# test2.net
KiCad netlist of a schematic drawn in EAGLE
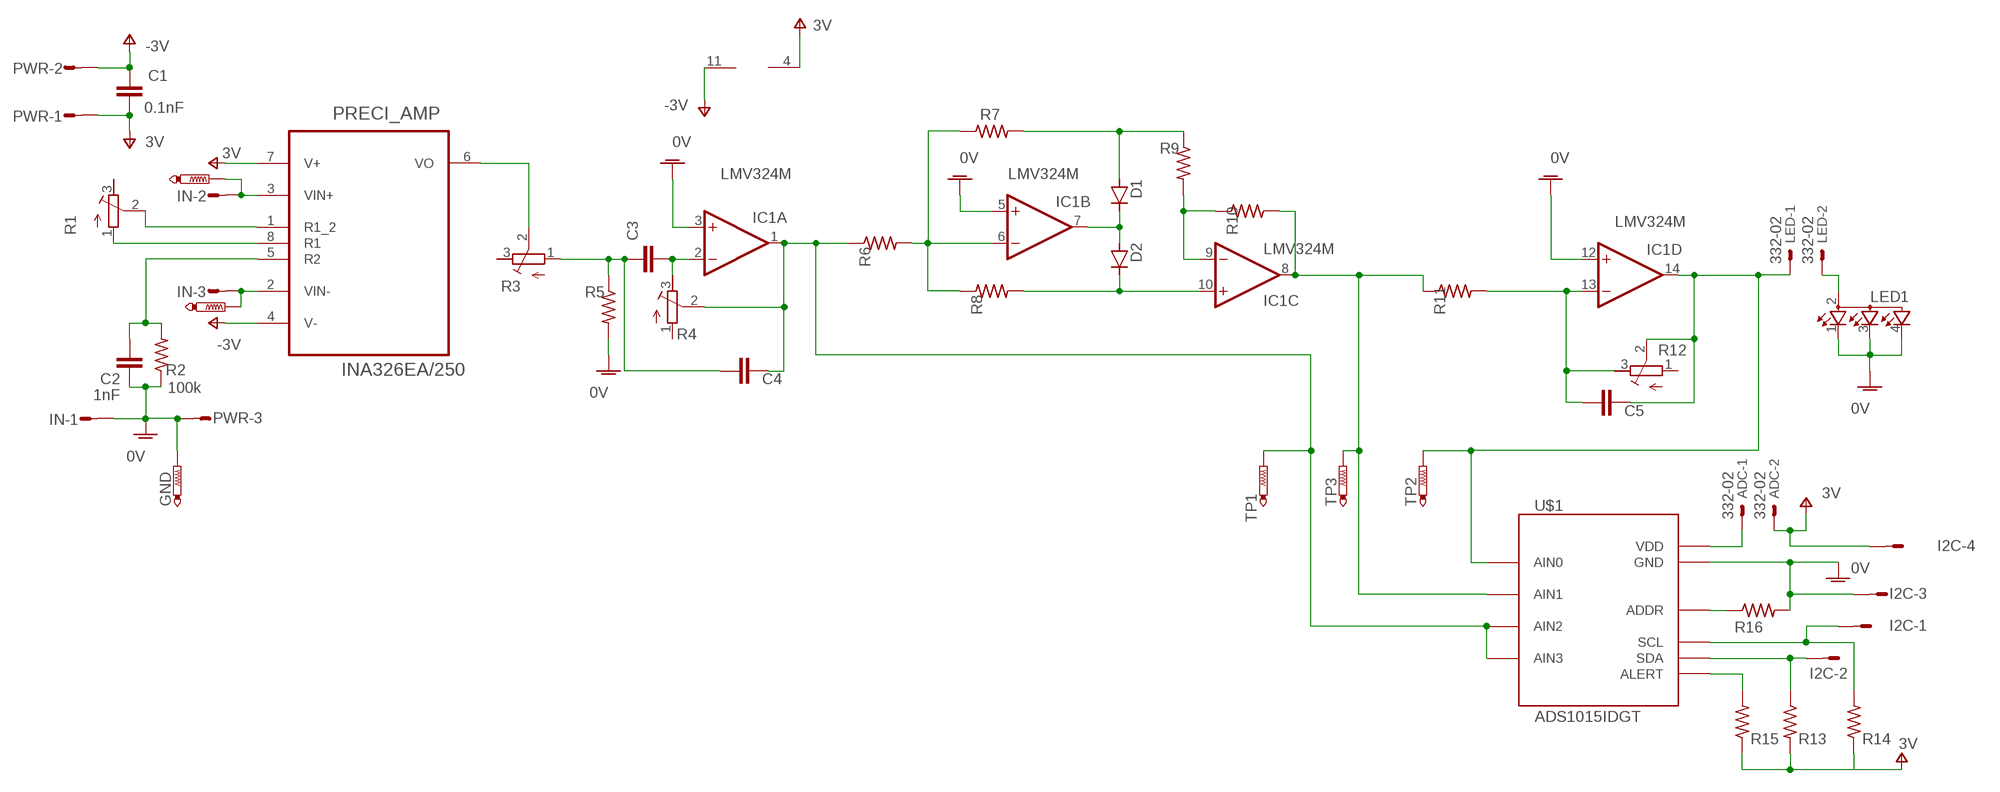
[diagram p0: schematic, sheet 1]

(export (version "E")
  (design (tool "Eeschema 10.0.6"))
  (components
    (comp (ref "ADC")
      (value "332-02")
      (footprint "eagle-import:332-02")
      (libsource (lib "eagle-import") (part "332-02"))
    )
    (comp (ref "C1")
      (value "0.1nF")
      (footprint "eagle-import:C0603")
      (libsource (lib "eagle-import") (part "C-EUC0603"))
    )
    (comp (ref "C2")
      (value "1nF")
      (footprint "eagle-import:C0603")
      (libsource (lib "eagle-import") (part "C-EUC0603"))
    )
    (comp (ref "C3")
      (value "0.1nF")
      (footprint "eagle-import:C0603")
      (libsource (lib "eagle-import") (part "C-EUC0603"))
    )
    (comp (ref "C4")
      (value "0.1nF")
      (footprint "eagle-import:C0603")
      (libsource (lib "eagle-import") (part "C-EUC0603"))
    )
    (comp (ref "C5")
      (value "0.1nF")
      (footprint "eagle-import:C0603")
      (libsource (lib "eagle-import") (part "C-EUC0603"))
    )
    (comp (ref "D1")
      (value "D-SOD-80")
      (footprint "eagle-import:SOD80")
      (libsource (lib "eagle-import") (part "D-SOD-80"))
    )
    (comp (ref "D2")
      (value "D-SOD-80")
      (footprint "eagle-import:SOD80")
      (libsource (lib "eagle-import") (part "D-SOD-80"))
    )
    (comp (ref "GND")
      (value "PTR1PAD1-13")
      (footprint "eagle-import:P1-13")
      (libsource (lib "eagle-import") (part "PTR1PAD1-13"))
    )
    (comp (ref "I2C")
      (value "MT6-4Y")
      (footprint "eagle-import:MT6-4Y")
      (libsource (lib "eagle-import") (part "MT6-4Y"))
    )
    (comp (ref "IC1")
      (value "LMV324M")
      (footprint "eagle-import:SO14")
      (fields (field (name "SPICEPREFIX") "J"))
      (libsource (lib "eagle-import") (part "LMV324?M"))
    )
    (comp (ref "IN")
      (value "MT6-3")
      (footprint "eagle-import:MT6-3")
      (libsource (lib "eagle-import") (part "MT6-3"))
    )
    (comp (ref "IN+")
      (value "PTR1PAD1-13")
      (footprint "eagle-import:P1-13")
      (libsource (lib "eagle-import") (part "PTR1PAD1-13"))
    )
    (comp (ref "IN-")
      (value "PTR1PAD1-13")
      (footprint "eagle-import:P1-13")
      (libsource (lib "eagle-import") (part "PTR1PAD1-13"))
    )
    (comp (ref "LED")
      (value "332-02")
      (footprint "eagle-import:332-02")
      (libsource (lib "eagle-import") (part "332-02"))
    )
    (comp (ref "LED1")
      (value "TOPLED-3")
      (footprint "eagle-import:P-LCC-4-3")
      (libsource (lib "eagle-import") (part "TOPLED-3"))
    )
    (comp (ref "PRECI_AMP")
      (value "INA326EA/250")
      (footprint "eagle-import:SOP65P490X110-8N")
      (fields (field (name "DIGI-KEY_PART_NUMBER") "296-15312-1-ND") (field (name "MF") "Texas Instruments"))
      (libsource (lib "eagle-import") (part "INA326EA/250"))
    )
    (comp (ref "PWR")
      (value "MT6-3")
      (footprint "eagle-import:MT6-3")
      (libsource (lib "eagle-import") (part "MT6-3"))
    )
    (comp (ref "R1")
      (value "R-TRIMM4G/J")
      (footprint "eagle-import:RTRIM4G_J")
      (libsource (lib "eagle-import") (part "R-TRIMM4G/J"))
    )
    (comp (ref "R2")
      (value "100k")
      (footprint "eagle-import:R0603")
      (libsource (lib "eagle-import") (part "R-US_R0603"))
    )
    (comp (ref "R3")
      (value "R-TRIMM4G/J")
      (footprint "eagle-import:RTRIM4G_J")
      (libsource (lib "eagle-import") (part "R-TRIMM4G/J"))
    )
    (comp (ref "R4")
      (value "R-TRIMM4G/J")
      (footprint "eagle-import:RTRIM4G_J")
      (libsource (lib "eagle-import") (part "R-TRIMM4G/J"))
    )
    (comp (ref "R5")
      (value "100k")
      (footprint "eagle-import:R0603")
      (libsource (lib "eagle-import") (part "R-US_R0603"))
    )
    (comp (ref "R6")
      (value "100k")
      (footprint "eagle-import:R0603")
      (libsource (lib "eagle-import") (part "R-US_R0603"))
    )
    (comp (ref "R7")
      (value "100k")
      (footprint "eagle-import:R0603")
      (libsource (lib "eagle-import") (part "R-US_R0603"))
    )
    (comp (ref "R8")
      (value "100k")
      (footprint "eagle-import:R0603")
      (libsource (lib "eagle-import") (part "R-US_R0603"))
    )
    (comp (ref "R9")
      (value "100k")
      (footprint "eagle-import:R0603")
      (libsource (lib "eagle-import") (part "R-US_R0603"))
    )
    (comp (ref "R10")
      (value "100k")
      (footprint "eagle-import:R0603")
      (libsource (lib "eagle-import") (part "R-US_R0603"))
    )
    (comp (ref "R11")
      (value "100k")
      (footprint "eagle-import:R0603")
      (libsource (lib "eagle-import") (part "R-US_R0603"))
    )
    (comp (ref "R12")
      (value "R-TRIMM4G/J")
      (footprint "eagle-import:RTRIM4G_J")
      (libsource (lib "eagle-import") (part "R-TRIMM4G/J"))
    )
    (comp (ref "R13")
      (value "100k")
      (footprint "eagle-import:R0603")
      (libsource (lib "eagle-import") (part "R-US_R0603"))
    )
    (comp (ref "R14")
      (value "100k")
      (footprint "eagle-import:R0603")
      (libsource (lib "eagle-import") (part "R-US_R0603"))
    )
    (comp (ref "R15")
      (value "100k")
      (footprint "eagle-import:R0603")
      (libsource (lib "eagle-import") (part "R-US_R0603"))
    )
    (comp (ref "R16")
      (value "100k")
      (footprint "eagle-import:R0603")
      (libsource (lib "eagle-import") (part "R-US_R0603"))
    )
    (comp (ref "TP1")
      (value "PTR1PAD1-13")
      (footprint "eagle-import:P1-13")
      (libsource (lib "eagle-import") (part "PTR1PAD1-13"))
    )
    (comp (ref "TP2")
      (value "PTR1PAD1-13")
      (footprint "eagle-import:P1-13")
      (libsource (lib "eagle-import") (part "PTR1PAD1-13"))
    )
    (comp (ref "TP3")
      (value "PTR1PAD1-13")
      (footprint "eagle-import:P1-13")
      (libsource (lib "eagle-import") (part "PTR1PAD1-13"))
    )
    (comp (ref "U$1")
      (value "ADS1015IDGT")
      (footprint "eagle-import:MSOP10_0.5")
      (fields (field (name "MF") "Texas Instruments") (field (name "MP") "ADS1015"))
      (libsource (lib "eagle-import") (part "ADS1015IDGT"))
    )
  )
  (nets
    (net (code "1") (name "-3V") (class "Default")
      (node (ref "C1") (pin "2") (pinfunction "2_2") (pintype "passive"))
      (node (ref "IC1") (pin "11") (pinfunction "V-_11") (pintype "power_in"))
      (node (ref "PRECI_AMP") (pin "4") (pinfunction "V-_4") (pintype "power_in"))
      (node (ref "PWR") (pin "2") (pinfunction "S_2") (pintype "passive"))
    )
    (net (code "2") (name "0V") (class "Default")
      (node (ref "C2") (pin "1") (pinfunction "1_1") (pintype "passive"))
      (node (ref "GND") (pin "TP") (pinfunction "TP_TP") (pintype "input"))
      (node (ref "I2C") (pin "3") (pinfunction "S_3") (pintype "passive"))
      (node (ref "IC1") (pin "12") (pinfunction "+IN_12") (pintype "input"))
      (node (ref "IC1") (pin "3") (pinfunction "+IN_3") (pintype "input"))
      (node (ref "IC1") (pin "5") (pinfunction "+IN_5") (pintype "input"))
      (node (ref "IN") (pin "1") (pinfunction "S_1") (pintype "passive"))
      (node (ref "LED1") (pin "1") (pinfunction "CRED_1") (pintype "passive"))
      (node (ref "LED1") (pin "3") (pinfunction "CBLUE_3") (pintype "passive"))
      (node (ref "LED1") (pin "4") (pinfunction "CGREEN_4") (pintype "passive"))
      (node (ref "PWR") (pin "3") (pinfunction "S_3") (pintype "passive"))
      (node (ref "R16") (pin "2") (pinfunction "2_2") (pintype "passive"))
      (node (ref "R2") (pin "1") (pinfunction "1_1") (pintype "passive"))
      (node (ref "R5") (pin "2") (pinfunction "2_2") (pintype "passive"))
      (node (ref "U$1") (pin "3") (pinfunction "GND_3") (pintype "power_in"))
    )
    (net (code "3") (name "3V") (class "Default")
      (node (ref "ADC") (pin "2") (pinfunction "S_2") (pintype "passive"))
      (node (ref "C1") (pin "1") (pinfunction "1_1") (pintype "passive"))
      (node (ref "I2C") (pin "4") (pinfunction "S_4") (pintype "passive"))
      (node (ref "IC1") (pin "4") (pinfunction "V+_4") (pintype "power_in"))
      (node (ref "PRECI_AMP") (pin "7") (pinfunction "V+_7") (pintype "power_in"))
      (node (ref "PWR") (pin "1") (pinfunction "S_1") (pintype "passive"))
      (node (ref "R13") (pin "2") (pinfunction "2_2") (pintype "passive"))
      (node (ref "R14") (pin "1") (pinfunction "1_1") (pintype "passive"))
      (node (ref "R15") (pin "1") (pinfunction "1_1") (pintype "passive"))
    )
    (net (code "4") (name "Net-(ADCA-S)") (class "Default")
      (node (ref "ADC") (pin "1") (pinfunction "S_1") (pintype "passive"))
      (node (ref "U$1") (pin "8") (pinfunction "VDD_8") (pintype "power_in"))
    )
    (net (code "5") (name "Net-(D1-A)") (class "Default")
      (node (ref "D1") (pin "2") (pinfunction "A_2") (pintype "passive"))
      (node (ref "R7") (pin "2") (pinfunction "2_2") (pintype "passive"))
      (node (ref "R9") (pin "1") (pinfunction "1_1") (pintype "passive"))
    )
    (net (code "6") (name "Net-(D1-C)") (class "Default")
      (node (ref "D1") (pin "1") (pinfunction "C_1") (pintype "passive"))
      (node (ref "D2") (pin "2") (pinfunction "A_2") (pintype "passive"))
      (node (ref "IC1") (pin "7") (pinfunction "OUT_7") (pintype "output"))
    )
    (net (code "7") (name "Net-(D2-C)") (class "Default")
      (node (ref "D2") (pin "1") (pinfunction "C_1") (pintype "passive"))
      (node (ref "IC1") (pin "10") (pinfunction "+IN_10") (pintype "input"))
      (node (ref "R8") (pin "2") (pinfunction "2_2") (pintype "passive"))
    )
    (net (code "8") (name "Net-(I2CA-S)") (class "Default")
      (node (ref "I2C") (pin "1") (pinfunction "S_1") (pintype "passive"))
      (node (ref "R14") (pin "2") (pinfunction "2_2") (pintype "passive"))
      (node (ref "U$1") (pin "10") (pinfunction "SCL_10") (pintype "bidirectional"))
    )
    (net (code "9") (name "Net-(I2CB-S)") (class "Default")
      (node (ref "I2C") (pin "2") (pinfunction "S_2") (pintype "passive"))
      (node (ref "R13") (pin "1") (pinfunction "1_1") (pintype "passive"))
      (node (ref "U$1") (pin "9") (pinfunction "SDA_9") (pintype "bidirectional"))
    )
    (net (code "10") (name "Net-(IC1A--IN)") (class "Default")
      (node (ref "C3") (pin "1") (pinfunction "1_1") (pintype "passive"))
      (node (ref "IC1") (pin "2") (pinfunction "-IN_2") (pintype "input"))
      (node (ref "R4") (pin "3") (pinfunction "E_3") (pintype "passive"))
    )
    (net (code "11") (name "Net-(IC1A-OUT)") (class "Default")
      (node (ref "C4") (pin "1") (pinfunction "1_1") (pintype "passive"))
      (node (ref "IC1") (pin "1") (pinfunction "OUT_1") (pintype "output"))
      (node (ref "R4") (pin "2") (pinfunction "S_2") (pintype "passive"))
      (node (ref "R6") (pin "1") (pinfunction "1_1") (pintype "passive"))
      (node (ref "TP1") (pin "TP") (pinfunction "TP_TP") (pintype "input"))
      (node (ref "U$1") (pin "6") (pinfunction "AIN2_6") (pintype "input"))
      (node (ref "U$1") (pin "7") (pinfunction "AIN3_7") (pintype "input"))
    )
    (net (code "12") (name "Net-(IC1B--IN)") (class "Default")
      (node (ref "IC1") (pin "6") (pinfunction "-IN_6") (pintype "input"))
      (node (ref "R6") (pin "2") (pinfunction "2_2") (pintype "passive"))
      (node (ref "R7") (pin "1") (pinfunction "1_1") (pintype "passive"))
      (node (ref "R8") (pin "1") (pinfunction "1_1") (pintype "passive"))
    )
    (net (code "13") (name "Net-(IC1C--IN)") (class "Default")
      (node (ref "IC1") (pin "9") (pinfunction "-IN_9") (pintype "input"))
      (node (ref "R10") (pin "1") (pinfunction "1_1") (pintype "passive"))
      (node (ref "R9") (pin "2") (pinfunction "2_2") (pintype "passive"))
    )
    (net (code "14") (name "Net-(IC1C-OUT)") (class "Default")
      (node (ref "IC1") (pin "8") (pinfunction "OUT_8") (pintype "output"))
      (node (ref "R10") (pin "2") (pinfunction "2_2") (pintype "passive"))
      (node (ref "R11") (pin "1") (pinfunction "1_1") (pintype "passive"))
      (node (ref "TP3") (pin "TP") (pinfunction "TP_TP") (pintype "input"))
      (node (ref "U$1") (pin "5") (pinfunction "AIN1_5") (pintype "input"))
    )
    (net (code "15") (name "Net-(IC1D--IN)") (class "Default")
      (node (ref "C5") (pin "2") (pinfunction "2_2") (pintype "passive"))
      (node (ref "IC1") (pin "13") (pinfunction "-IN_13") (pintype "input"))
      (node (ref "R11") (pin "2") (pinfunction "2_2") (pintype "passive"))
      (node (ref "R12") (pin "3") (pinfunction "E_3") (pintype "passive"))
    )
    (net (code "16") (name "Net-(IC1D-OUT)") (class "Default")
      (node (ref "C5") (pin "1") (pinfunction "1_1") (pintype "passive"))
      (node (ref "IC1") (pin "14") (pinfunction "OUT_14") (pintype "output"))
      (node (ref "LED") (pin "1") (pinfunction "S_1") (pintype "passive"))
      (node (ref "R12") (pin "2") (pinfunction "S_2") (pintype "passive"))
      (node (ref "TP2") (pin "TP") (pinfunction "TP_TP") (pintype "input"))
      (node (ref "U$1") (pin "4") (pinfunction "AIN0_4") (pintype "input"))
    )
    (net (code "17") (name "Net-(INB-S)") (class "Default")
      (node (ref "IN") (pin "2") (pinfunction "S_2") (pintype "passive"))
      (node (ref "IN+") (pin "TP") (pinfunction "TP_TP") (pintype "input"))
      (node (ref "PRECI_AMP") (pin "3") (pinfunction "VIN+_3") (pintype "input"))
    )
    (net (code "18") (name "Net-(INC-S)") (class "Default")
      (node (ref "IN") (pin "3") (pinfunction "S_3") (pintype "passive"))
      (node (ref "IN-") (pin "TP") (pinfunction "TP_TP") (pintype "input"))
      (node (ref "PRECI_AMP") (pin "2") (pinfunction "VIN-_2") (pintype "input"))
    )
    (net (code "19") (name "Net-(LED1-A2)") (class "Default")
      (node (ref "LED") (pin "2") (pinfunction "S_2") (pintype "passive"))
      (node (ref "LED1") (pin "2") (pinfunction "A2_2") (pintype "passive"))
    )
    (net (code "20") (name "Net-(PRECI_AMP-R1)") (class "Default")
      (node (ref "PRECI_AMP") (pin "8") (pinfunction "R1_8") (pintype "input"))
      (node (ref "R1") (pin "1") (pinfunction "A_1") (pintype "passive"))
    )
    (net (code "21") (name "Net-(PRECI_AMP-R1_2)") (class "Default")
      (node (ref "PRECI_AMP") (pin "1") (pinfunction "R1_2_1") (pintype "input"))
      (node (ref "R1") (pin "2") (pinfunction "S_2") (pintype "passive"))
    )
    (net (code "22") (name "Net-(PRECI_AMP-R2)") (class "Default")
      (node (ref "C2") (pin "2") (pinfunction "2_2") (pintype "passive"))
      (node (ref "PRECI_AMP") (pin "5") (pinfunction "R2_5") (pintype "input"))
      (node (ref "R2") (pin "2") (pinfunction "2_2") (pintype "passive"))
    )
    (net (code "23") (name "Net-(PRECI_AMP-VO)") (class "Default")
      (node (ref "PRECI_AMP") (pin "6") (pinfunction "VO_6") (pintype "output"))
      (node (ref "R3") (pin "2") (pinfunction "S_2") (pintype "passive"))
    )
    (net (code "24") (name "Net-(R3-A)") (class "Default")
      (node (ref "C3") (pin "2") (pinfunction "2_2") (pintype "passive"))
      (node (ref "C4") (pin "2") (pinfunction "2_2") (pintype "passive"))
      (node (ref "R3") (pin "1") (pinfunction "A_1") (pintype "passive"))
      (node (ref "R5") (pin "1") (pinfunction "1_1") (pintype "passive"))
    )
    (net (code "25") (name "Net-(U$1-ADDR)") (class "Default")
      (node (ref "R16") (pin "1") (pinfunction "1_1") (pintype "passive"))
      (node (ref "U$1") (pin "1") (pinfunction "ADDR_1") (pintype "input"))
    )
    (net (code "26") (name "Net-(U$1-ALERT)") (class "Default")
      (node (ref "R15") (pin "2") (pinfunction "2_2") (pintype "passive"))
      (node (ref "U$1") (pin "2") (pinfunction "ALERT_2") (pintype "output"))
    )
    (net (code "27") (name "unconnected-(R1-E-Pad3)") (class "Default")
      (node (ref "R1") (pin "3") (pinfunction "E_3") (pintype "passive"))
    )
    (net (code "28") (name "unconnected-(R3-E-Pad3)") (class "Default")
      (node (ref "R3") (pin "3") (pinfunction "E_3") (pintype "passive"))
    )
    (net (code "29") (name "unconnected-(R4-A-Pad1)") (class "Default")
      (node (ref "R4") (pin "1") (pinfunction "A_1") (pintype "passive"))
    )
    (net (code "30") (name "unconnected-(R12-A-Pad1)") (class "Default")
      (node (ref "R12") (pin "1") (pinfunction "A_1") (pintype "passive"))
    )
  )
)
